# RGMII_PHY.net
KiCad netlist of a schematic drawn in Altium Designer
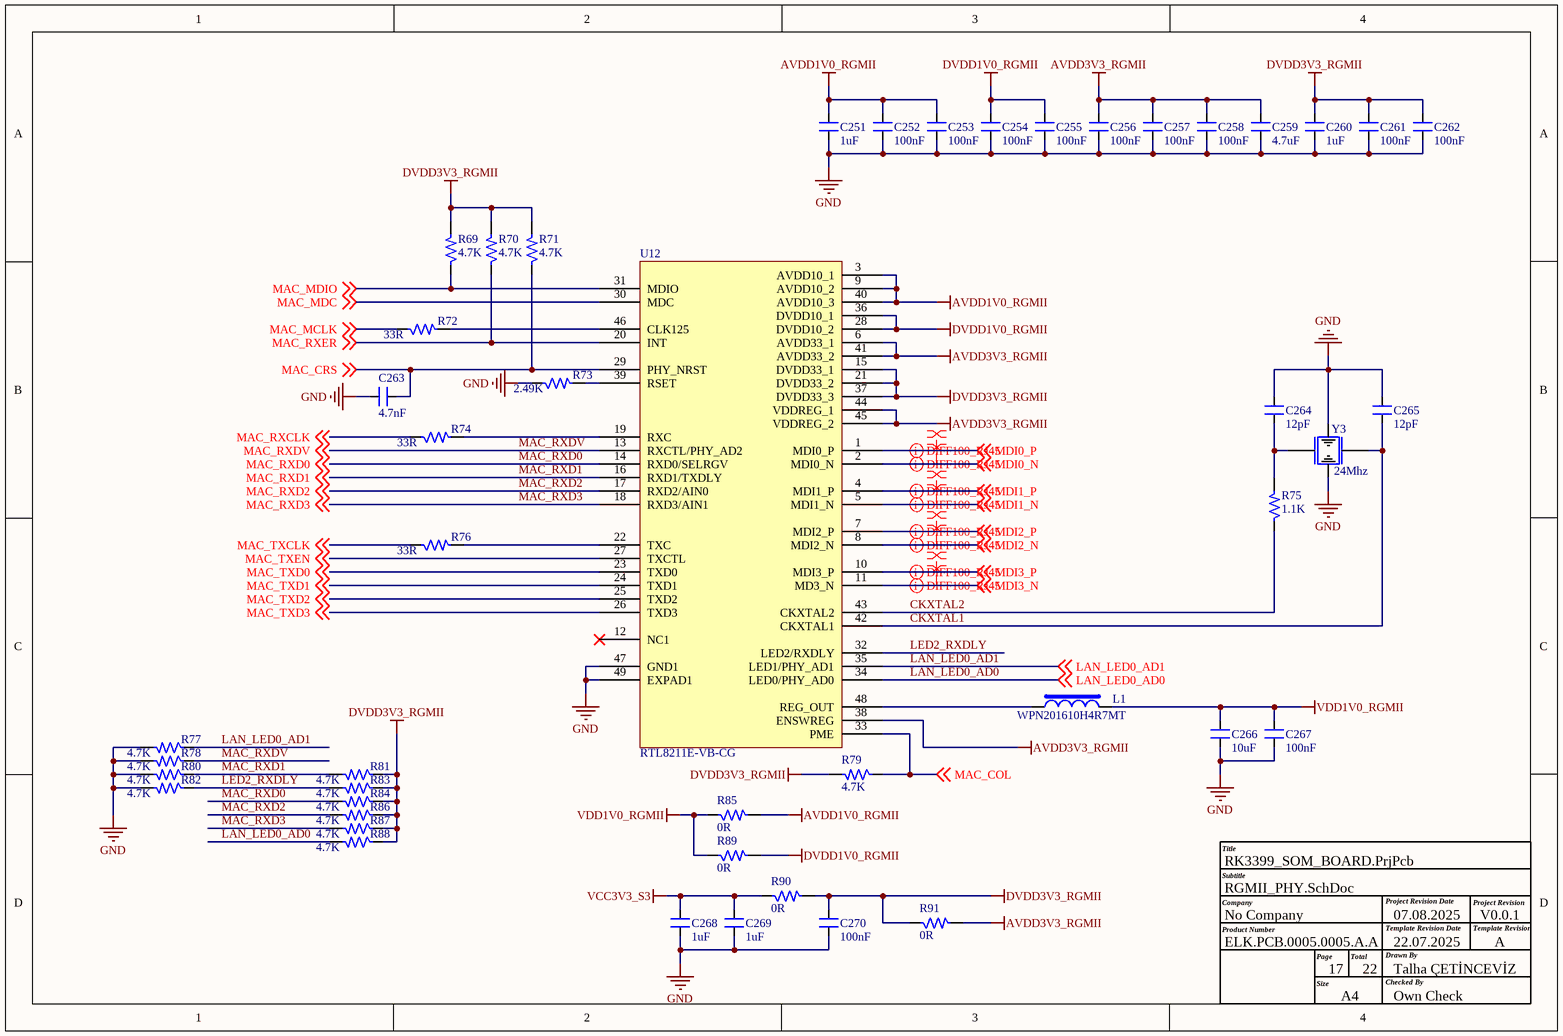
[diagram p0: RGMII_PHY.SchDoc]

(export (version "E")
  (design (tool "Eeschema 10.0.6"))
  (components
    (comp (ref "C251")
      (value "1uF")
      (footprint "CAP_0201")
      (description "1µF ±20% 16V Ceramic Capacitor X5R 0201 (0603 Metric)")
      (fields
        (field (name "MANUFACTURER") "Samsung Electro-Mechanics")
        (field (name "MANUFACTURER PART NUMBER") "CL03A105MO3NRNH")
      )
      (libsource (lib "EsteemPCB_SOM_Course_intlib") (part "CAP_1uF-16V-10%-0201"))
    )
    (comp (ref "C252")
      (value "100nF")
      (footprint "CAP_0201")
      (description "0.1µF ±10% 25V Ceramic Capacitor X5R 0201 (0603 Metric)")
      (fields
        (field (name "MANUFACTURER") "TDK Corporation")
        (field (name "MANUFACTURER PART NUMBER") "C0603X5R1E104K030BB")
      )
      (libsource (lib "EsteemPCB_SOM_Course_intlib") (part "CAP_100nF-25V-10%-0201"))
    )
    (comp (ref "C253")
      (value "100nF")
      (footprint "CAP_0201")
      (description "0.1µF ±10% 25V Ceramic Capacitor X5R 0201 (0603 Metric)")
      (fields
        (field (name "MANUFACTURER") "TDK Corporation")
        (field (name "MANUFACTURER PART NUMBER") "C0603X5R1E104K030BB")
      )
      (libsource (lib "EsteemPCB_SOM_Course_intlib") (part "CAP_100nF-25V-10%-0201"))
    )
    (comp (ref "C254")
      (value "100nF")
      (footprint "CAP_0201")
      (description "0.1µF ±10% 25V Ceramic Capacitor X5R 0201 (0603 Metric)")
      (fields
        (field (name "MANUFACTURER") "TDK Corporation")
        (field (name "MANUFACTURER PART NUMBER") "C0603X5R1E104K030BB")
      )
      (libsource (lib "EsteemPCB_SOM_Course_intlib") (part "CAP_100nF-25V-10%-0201"))
    )
    (comp (ref "C255")
      (value "100nF")
      (footprint "CAP_0201")
      (description "0.1µF ±10% 25V Ceramic Capacitor X5R 0201 (0603 Metric)")
      (fields
        (field (name "MANUFACTURER") "TDK Corporation")
        (field (name "MANUFACTURER PART NUMBER") "C0603X5R1E104K030BB")
      )
      (libsource (lib "EsteemPCB_SOM_Course_intlib") (part "CAP_100nF-25V-10%-0201"))
    )
    (comp (ref "C256")
      (value "100nF")
      (footprint "CAP_0201")
      (description "0.1µF ±10% 25V Ceramic Capacitor X5R 0201 (0603 Metric)")
      (fields
        (field (name "MANUFACTURER") "TDK Corporation")
        (field (name "MANUFACTURER PART NUMBER") "C0603X5R1E104K030BB")
      )
      (libsource (lib "EsteemPCB_SOM_Course_intlib") (part "CAP_100nF-25V-10%-0201"))
    )
    (comp (ref "C257")
      (value "100nF")
      (footprint "CAP_0201")
      (description "0.1µF ±10% 25V Ceramic Capacitor X5R 0201 (0603 Metric)")
      (fields
        (field (name "MANUFACTURER") "TDK Corporation")
        (field (name "MANUFACTURER PART NUMBER") "C0603X5R1E104K030BB")
      )
      (libsource (lib "EsteemPCB_SOM_Course_intlib") (part "CAP_100nF-25V-10%-0201"))
    )
    (comp (ref "C258")
      (value "100nF")
      (footprint "CAP_0201")
      (description "0.1µF ±10% 25V Ceramic Capacitor X5R 0201 (0603 Metric)")
      (fields
        (field (name "MANUFACTURER") "TDK Corporation")
        (field (name "MANUFACTURER PART NUMBER") "C0603X5R1E104K030BB")
      )
      (libsource (lib "EsteemPCB_SOM_Course_intlib") (part "CAP_100nF-25V-10%-0201"))
    )
    (comp (ref "C259")
      (value "4.7uF")
      (footprint "CAP_0201")
      (description "4.7µF ±20% 6.3V Ceramic Capacitor X5R 0201 (0603 Metric)")
      (fields
        (field (name "MANUFACTURER") "Murata Electronics")
        (field (name "MANUFACTURER PART NUMBER") "GRM035R60J475ME15D")
      )
      (libsource (lib "EsteemPCB_SOM_Course_intlib") (part "CAP_4.7uF-6.3V-20%-0201"))
    )
    (comp (ref "C260")
      (value "1uF")
      (footprint "CAP_0201")
      (description "1µF ±20% 16V Ceramic Capacitor X5R 0201 (0603 Metric)")
      (fields
        (field (name "MANUFACTURER") "Samsung Electro-Mechanics")
        (field (name "MANUFACTURER PART NUMBER") "CL03A105MO3NRNH")
      )
      (libsource (lib "EsteemPCB_SOM_Course_intlib") (part "CAP_1uF-16V-10%-0201"))
    )
    (comp (ref "C261")
      (value "100nF")
      (footprint "CAP_0201")
      (description "0.1µF ±10% 25V Ceramic Capacitor X5R 0201 (0603 Metric)")
      (fields
        (field (name "MANUFACTURER") "TDK Corporation")
        (field (name "MANUFACTURER PART NUMBER") "C0603X5R1E104K030BB")
      )
      (libsource (lib "EsteemPCB_SOM_Course_intlib") (part "CAP_100nF-25V-10%-0201"))
    )
    (comp (ref "C262")
      (value "100nF")
      (footprint "CAP_0201")
      (description "0.1µF ±10% 25V Ceramic Capacitor X5R 0201 (0603 Metric)")
      (fields
        (field (name "MANUFACTURER") "TDK Corporation")
        (field (name "MANUFACTURER PART NUMBER") "C0603X5R1E104K030BB")
      )
      (libsource (lib "EsteemPCB_SOM_Course_intlib") (part "CAP_100nF-25V-10%-0201"))
    )
    (comp (ref "C263")
      (value "4.7nF")
      (footprint "CAP_0201")
      (description "4700pF ±10% 10V Ceramic Capacitor X7R 0201 (0603 Metric)")
      (fields
        (field (name "MANUFACTURER") "AVX Corporation")
        (field (name "MANUFACTURER PART NUMBER") "0201ZC472KAT2A")
      )
      (libsource (lib "EsteemPCB_SOM_Course_intlib") (part "CAP_4.7nF-10V-10%-0201"))
    )
    (comp (ref "C264")
      (value "12pF")
      (footprint "CAP_0201")
      (description "12pF ±10% 16V Ceramic Capacitor C0G, NP0 0201 (0603 Metric)")
      (fields
        (field (name "MANUFACTURER") "AVX Corporation")
        (field (name "MANUFACTURER PART NUMBER") "0201YA120KAT2A")
      )
      (libsource (lib "EsteemPCB_SOM_Course_intlib") (part "CAP_12pF-16V-10%-0201"))
    )
    (comp (ref "C265")
      (value "12pF")
      (footprint "CAP_0201")
      (description "12pF ±10% 16V Ceramic Capacitor C0G, NP0 0201 (0603 Metric)")
      (fields
        (field (name "MANUFACTURER") "AVX Corporation")
        (field (name "MANUFACTURER PART NUMBER") "0201YA120KAT2A")
      )
      (libsource (lib "EsteemPCB_SOM_Course_intlib") (part "CAP_12pF-16V-10%-0201"))
    )
    (comp (ref "C266")
      (value "10uF")
      (footprint "CAP_0402")
      (description "10µF ±20% 10V Ceramic Capacitor X5R 0402 (1005 Metric)")
      (fields
        (field (name "MANUFACTURER PART NUMBER") "CL05A106MP5NUNC")
        (field (name "MANUFACTURER") "Samsung Electro-Mechanics")
      )
      (libsource (lib "EsteemPCB_SOM_Course_intlib") (part "CAP_10uF-10V-20%-0402"))
    )
    (comp (ref "C267")
      (value "100nF")
      (footprint "CAP_0201")
      (description "0.1µF ±10% 25V Ceramic Capacitor X5R 0201 (0603 Metric)")
      (fields
        (field (name "MANUFACTURER") "TDK Corporation")
        (field (name "MANUFACTURER PART NUMBER") "C0603X5R1E104K030BB")
      )
      (libsource (lib "EsteemPCB_SOM_Course_intlib") (part "CAP_100nF-25V-10%-0201"))
    )
    (comp (ref "C268")
      (value "1uF")
      (footprint "CAP_0201")
      (description "1µF ±20% 16V Ceramic Capacitor X5R 0201 (0603 Metric)")
      (fields
        (field (name "MANUFACTURER") "Samsung Electro-Mechanics")
        (field (name "MANUFACTURER PART NUMBER") "CL03A105MO3NRNH")
      )
      (libsource (lib "EsteemPCB_SOM_Course_intlib") (part "CAP_1uF-16V-10%-0201"))
    )
    (comp (ref "C269")
      (value "1uF")
      (footprint "CAP_0201")
      (description "1µF ±20% 16V Ceramic Capacitor X5R 0201 (0603 Metric)")
      (fields
        (field (name "MANUFACTURER") "Samsung Electro-Mechanics")
        (field (name "MANUFACTURER PART NUMBER") "CL03A105MO3NRNH")
      )
      (libsource (lib "EsteemPCB_SOM_Course_intlib") (part "CAP_1uF-16V-10%-0201"))
    )
    (comp (ref "C270")
      (value "100nF")
      (footprint "CAP_0201")
      (description "0.1µF ±10% 25V Ceramic Capacitor X5R 0201 (0603 Metric)")
      (fields
        (field (name "MANUFACTURER") "TDK Corporation")
        (field (name "MANUFACTURER PART NUMBER") "C0603X5R1E104K030BB")
      )
      (libsource (lib "EsteemPCB_SOM_Course_intlib") (part "CAP_100nF-25V-10%-0201"))
    )
    (comp (ref "L1")
      (value "WPN201610H4R7MT")
      (footprint "IND_62.9_110X86.6_SMD")
      (description "4.7uH ±20% 900mA 425mΩ SMD,2.0x1.6x1.0mm Power Inductors RoHS")
      (fields (field (name "MANUFACTURER") "Sunlord"))
      (libsource (lib "EsteemPCB_SOM_Course_intlib") (part "IND_4.7uH-0.9A-20%-SMD"))
    )
    (comp (ref "R69")
      (value "4.7K")
      (footprint "RES_0201")
      (description "4.02 kOhms ±1% 0.05W, 1/20W Chip Resistor 0201 (0603 Metric) Thick Film")
      (fields
        (field (name "MANUFACTURER") "Yageo")
        (field (name "MANUFACTURER PART NUMBER") "RC0201FR-074K02L")
      )
      (libsource (lib "EsteemPCB_SOM_Course_intlib") (part "RES_4.7K-0.1W-1%-0201"))
    )
    (comp (ref "R70")
      (value "4.7K")
      (footprint "RES_0201")
      (description "4.02 kOhms ±1% 0.05W, 1/20W Chip Resistor 0201 (0603 Metric) Thick Film")
      (fields
        (field (name "MANUFACTURER") "Yageo")
        (field (name "MANUFACTURER PART NUMBER") "RC0201FR-074K02L")
      )
      (libsource (lib "EsteemPCB_SOM_Course_intlib") (part "RES_4.7K-0.1W-1%-0201"))
    )
    (comp (ref "R71")
      (value "4.7K")
      (footprint "RES_0201")
      (description "4.02 kOhms ±1% 0.05W, 1/20W Chip Resistor 0201 (0603 Metric) Thick Film")
      (fields
        (field (name "MANUFACTURER") "Yageo")
        (field (name "MANUFACTURER PART NUMBER") "RC0201FR-074K02L")
      )
      (libsource (lib "EsteemPCB_SOM_Course_intlib") (part "RES_4.7K-0.1W-1%-0201"))
    )
    (comp (ref "R72")
      (value "33R")
      (footprint "RES_0201")
      (description "33 Ohms ±1% 0.05W, 1/20W Chip Resistor 0201 (0603 Metric) Thick Film")
      (fields
        (field (name "MANUFACTURER") "Yageo")
        (field (name "MANUFACTURER PART NUMBER") "RC0201FR-0733RL")
      )
      (libsource (lib "EsteemPCB_SOM_Course_intlib") (part "RES_33R-0.05W-1%-0201"))
    )
    (comp (ref "R73")
      (value "2.49K")
      (footprint "RES_0201")
      (description "2.49 kOhms ±1% 0.05W, 1/20W Chip Resistor 0201 (0603 Metric) Automotive AEC-Q200 Thick Film")
      (fields
        (field (name "MANUFACTURER") "Panasonic Electronic Components")
        (field (name "MANUFACTURER PART NUMBER") "ERJ-1GNF2491C")
      )
      (libsource (lib "EsteemPCB_SOM_Course_intlib") (part "RES_2.49K-0.05W-1%-0201"))
    )
    (comp (ref "R74")
      (value "33R")
      (footprint "RES_0201")
      (description "33 Ohms ±1% 0.05W, 1/20W Chip Resistor 0201 (0603 Metric) Thick Film")
      (fields
        (field (name "MANUFACTURER") "Yageo")
        (field (name "MANUFACTURER PART NUMBER") "RC0201FR-0733RL")
      )
      (libsource (lib "EsteemPCB_SOM_Course_intlib") (part "RES_33R-0.05W-1%-0201"))
    )
    (comp (ref "R75")
      (value "1.1K")
      (footprint "RES_0201")
      (description "1.1 kOhms ±1% 0.05W, 1/20W Chip Resistor 0201 (0603 Metric) Automotive AEC-Q200 Thick Film")
      (fields
        (field (name "MANUFACTURER") "Panasonic Electronic Components")
        (field (name "MANUFACTURER PART NUMBER") "ERJ-1GNF1101C")
      )
      (libsource (lib "EsteemPCB_SOM_Course_intlib") (part "RES_1.1K-0.05W-1%-0201"))
    )
    (comp (ref "R76")
      (value "33R")
      (footprint "RES_0201")
      (description "33 Ohms ±1% 0.05W, 1/20W Chip Resistor 0201 (0603 Metric) Thick Film")
      (fields
        (field (name "MANUFACTURER") "Yageo")
        (field (name "MANUFACTURER PART NUMBER") "RC0201FR-0733RL")
      )
      (libsource (lib "EsteemPCB_SOM_Course_intlib") (part "RES_33R-0.05W-1%-0201"))
    )
    (comp (ref "R77")
      (value "4.7K")
      (footprint "RES_0201")
      (description "4.02 kOhms ±1% 0.05W, 1/20W Chip Resistor 0201 (0603 Metric) Thick Film")
      (fields
        (field (name "MANUFACTURER") "Yageo")
        (field (name "MANUFACTURER PART NUMBER") "RC0201FR-074K02L")
      )
      (libsource (lib "EsteemPCB_SOM_Course_intlib") (part "RES_4.7K-0.1W-1%-0201"))
    )
    (comp (ref "R78")
      (value "4.7K")
      (footprint "RES_0201")
      (description "4.02 kOhms ±1% 0.05W, 1/20W Chip Resistor 0201 (0603 Metric) Thick Film")
      (fields
        (field (name "MANUFACTURER") "Yageo")
        (field (name "MANUFACTURER PART NUMBER") "RC0201FR-074K02L")
      )
      (libsource (lib "EsteemPCB_SOM_Course_intlib") (part "RES_4.7K-0.1W-1%-0201"))
    )
    (comp (ref "R79")
      (value "4.7K")
      (footprint "RES_0201")
      (description "4.02 kOhms ±1% 0.05W, 1/20W Chip Resistor 0201 (0603 Metric) Thick Film")
      (fields
        (field (name "MANUFACTURER") "Yageo")
        (field (name "MANUFACTURER PART NUMBER") "RC0201FR-074K02L")
      )
      (libsource (lib "EsteemPCB_SOM_Course_intlib") (part "RES_4.7K-0.1W-1%-0201"))
    )
    (comp (ref "R80")
      (value "4.7K")
      (footprint "RES_0201")
      (description "4.02 kOhms ±1% 0.05W, 1/20W Chip Resistor 0201 (0603 Metric) Thick Film")
      (fields
        (field (name "MANUFACTURER") "Yageo")
        (field (name "MANUFACTURER PART NUMBER") "RC0201FR-074K02L")
      )
      (libsource (lib "EsteemPCB_SOM_Course_intlib") (part "RES_4.7K-0.1W-1%-0201"))
    )
    (comp (ref "R81")
      (value "4.7K")
      (footprint "RES_0201")
      (description "4.02 kOhms ±1% 0.05W, 1/20W Chip Resistor 0201 (0603 Metric) Thick Film")
      (fields
        (field (name "MANUFACTURER") "Yageo")
        (field (name "MANUFACTURER PART NUMBER") "RC0201FR-074K02L")
      )
      (libsource (lib "EsteemPCB_SOM_Course_intlib") (part "RES_4.7K-0.1W-1%-0201"))
    )
    (comp (ref "R82")
      (value "4.7K")
      (footprint "RES_0201")
      (description "4.02 kOhms ±1% 0.05W, 1/20W Chip Resistor 0201 (0603 Metric) Thick Film")
      (fields
        (field (name "MANUFACTURER") "Yageo")
        (field (name "MANUFACTURER PART NUMBER") "RC0201FR-074K02L")
      )
      (libsource (lib "EsteemPCB_SOM_Course_intlib") (part "RES_4.7K-0.1W-1%-0201"))
    )
    (comp (ref "R83")
      (value "4.7K")
      (footprint "RES_0201")
      (description "4.02 kOhms ±1% 0.05W, 1/20W Chip Resistor 0201 (0603 Metric) Thick Film")
      (fields
        (field (name "MANUFACTURER") "Yageo")
        (field (name "MANUFACTURER PART NUMBER") "RC0201FR-074K02L")
      )
      (libsource (lib "EsteemPCB_SOM_Course_intlib") (part "RES_4.7K-0.1W-1%-0201"))
    )
    (comp (ref "R84")
      (value "4.7K")
      (footprint "RES_0201")
      (description "4.02 kOhms ±1% 0.05W, 1/20W Chip Resistor 0201 (0603 Metric) Thick Film")
      (fields
        (field (name "MANUFACTURER") "Yageo")
        (field (name "MANUFACTURER PART NUMBER") "RC0201FR-074K02L")
      )
      (libsource (lib "EsteemPCB_SOM_Course_intlib") (part "RES_4.7K-0.1W-1%-0201"))
    )
    (comp (ref "R85")
      (value "0R")
      (footprint "RES_0201")
      (description "0 Ohms Jumper 0.05W, 1/20W Chip Resistor 0201 (0603 Metric) Automotive AEC-Q200 Thick Film")
      (fields
        (field (name "MANUFACTURER") "Bourns Inc.")
        (field (name "MANUFACTURER PART NUMBER") "CR0201AJ/-000GLF")
      )
      (libsource (lib "EsteemPCB_SOM_Course_intlib") (part "RES_0R-0.05W-1%-0201"))
    )
    (comp (ref "R86")
      (value "4.7K")
      (footprint "RES_0201")
      (description "4.02 kOhms ±1% 0.05W, 1/20W Chip Resistor 0201 (0603 Metric) Thick Film")
      (fields
        (field (name "MANUFACTURER") "Yageo")
        (field (name "MANUFACTURER PART NUMBER") "RC0201FR-074K02L")
      )
      (libsource (lib "EsteemPCB_SOM_Course_intlib") (part "RES_4.7K-0.1W-1%-0201"))
    )
    (comp (ref "R87")
      (value "4.7K")
      (footprint "RES_0201")
      (description "4.02 kOhms ±1% 0.05W, 1/20W Chip Resistor 0201 (0603 Metric) Thick Film")
      (fields
        (field (name "MANUFACTURER") "Yageo")
        (field (name "MANUFACTURER PART NUMBER") "RC0201FR-074K02L")
      )
      (libsource (lib "EsteemPCB_SOM_Course_intlib") (part "RES_4.7K-0.1W-1%-0201"))
    )
    (comp (ref "R88")
      (value "4.7K")
      (footprint "RES_0201")
      (description "4.02 kOhms ±1% 0.05W, 1/20W Chip Resistor 0201 (0603 Metric) Thick Film")
      (fields
        (field (name "MANUFACTURER") "Yageo")
        (field (name "MANUFACTURER PART NUMBER") "RC0201FR-074K02L")
      )
      (libsource (lib "EsteemPCB_SOM_Course_intlib") (part "RES_4.7K-0.1W-1%-0201"))
    )
    (comp (ref "R89")
      (value "0R")
      (footprint "RES_0201")
      (description "0 Ohms Jumper 0.05W, 1/20W Chip Resistor 0201 (0603 Metric) Automotive AEC-Q200 Thick Film")
      (fields
        (field (name "MANUFACTURER") "Bourns Inc.")
        (field (name "MANUFACTURER PART NUMBER") "CR0201AJ/-000GLF")
      )
      (libsource (lib "EsteemPCB_SOM_Course_intlib") (part "RES_0R-0.05W-1%-0201"))
    )
    (comp (ref "R90")
      (value "0R")
      (footprint "RES_0201")
      (description "0 Ohms Jumper 0.05W, 1/20W Chip Resistor 0201 (0603 Metric) Automotive AEC-Q200 Thick Film")
      (fields
        (field (name "MANUFACTURER") "Bourns Inc.")
        (field (name "MANUFACTURER PART NUMBER") "CR0201AJ/-000GLF")
      )
      (libsource (lib "EsteemPCB_SOM_Course_intlib") (part "RES_0R-0.05W-1%-0201"))
    )
    (comp (ref "R91")
      (value "0R")
      (footprint "RES_0201")
      (description "0 Ohms Jumper 0.05W, 1/20W Chip Resistor 0201 (0603 Metric) Automotive AEC-Q200 Thick Film")
      (fields
        (field (name "MANUFACTURER") "Bourns Inc.")
        (field (name "MANUFACTURER PART NUMBER") "CR0201AJ/-000GLF")
      )
      (libsource (lib "EsteemPCB_SOM_Course_intlib") (part "RES_0R-0.05W-1%-0201"))
    )
    (comp (ref "U12")
      (value "RTL8211E-VB-CG")
      (footprint "QFN48_19.6_324X324_SMD")
      (fields (field (name "MANUFACTURER") "Realtek Semicon"))
      (libsource (lib "EsteemPCB_SOM_Course_intlib") (part "IC_RTL8211E-VB-CG"))
    )
    (comp (ref "Y3")
      (value "24Mhz")
      (footprint "XTAL_ABM8AIG-24.000MHZ-12-2Z-T3")
      (description "24MHz ±20ppm Crystal 12pF 50 Ohms 4-SMD, No Lead")
      (fields
        (field (name "MANUFACTURER") "Abracon LLC")
        (field (name "MANUFACTURER PART NUMBER") "ABM8AIG-24.000MHZ-12-2Z-T3")
      )
      (libsource (lib "EsteemPCB_SOM_Course_intlib") (part "XTAL_24Mhz-12pF-4-SMD"))
    )
  )
  (nets
    (net (code "1") (name "/CKXTAL1") (class "Default")
      (node (ref "C265") (pin "2") (pinfunction "2_2") (pintype "passive"))
      (node (ref "U12") (pin "42") (pinfunction "CKXTAL1_42") (pintype "passive"))
      (node (ref "Y3") (pin "1") (pinfunction "1_1") (pintype "passive"))
    )
    (net (code "2") (name "/CKXTAL2") (class "Default")
      (node (ref "R75") (pin "1") (pinfunction "1_1") (pintype "passive"))
      (node (ref "U12") (pin "43") (pinfunction "CKXTAL2_43") (pintype "passive"))
    )
    (net (code "3") (name "/LED2_RXDLY") (class "Default")
      (node (ref "R82") (pin "1") (pinfunction "1_1") (pintype "passive"))
      (node (ref "R83") (pin "2") (pinfunction "2_2") (pintype "passive"))
      (node (ref "U12") (pin "32") (pinfunction "LED2/RXDLY_32") (pintype "passive"))
    )
    (net (code "4") (name "AVDD1V0_RGMII") (class "Default")
      (node (ref "C251") (pin "2") (pinfunction "2_2") (pintype "passive"))
      (node (ref "C252") (pin "2") (pinfunction "2_2") (pintype "passive"))
      (node (ref "C253") (pin "2") (pinfunction "2_2") (pintype "passive"))
      (node (ref "R85") (pin "2") (pinfunction "2_2") (pintype "passive"))
      (node (ref "U12") (pin "3") (pinfunction "AVDD10_1_3") (pintype "passive"))
      (node (ref "U12") (pin "40") (pinfunction "AVDD10_3_40") (pintype "passive"))
      (node (ref "U12") (pin "9") (pinfunction "AVDD10_2_9") (pintype "passive"))
    )
    (net (code "5") (name "AVDD3V3_RGMII") (class "Default")
      (node (ref "C256") (pin "2") (pinfunction "2_2") (pintype "passive"))
      (node (ref "C257") (pin "2") (pinfunction "2_2") (pintype "passive"))
      (node (ref "C258") (pin "2") (pinfunction "2_2") (pintype "passive"))
      (node (ref "C259") (pin "2") (pinfunction "2_2") (pintype "passive"))
      (node (ref "R91") (pin "2") (pinfunction "2_2") (pintype "passive"))
      (node (ref "U12") (pin "38") (pinfunction "ENSWREG_38") (pintype "passive"))
      (node (ref "U12") (pin "41") (pinfunction "AVDD33_2_41") (pintype "passive"))
      (node (ref "U12") (pin "44") (pinfunction "VDDREG_1_44") (pintype "passive"))
      (node (ref "U12") (pin "45") (pinfunction "VDDREG_2_45") (pintype "passive"))
      (node (ref "U12") (pin "6") (pinfunction "AVDD33_1_6") (pintype "passive"))
    )
    (net (code "6") (name "DVDD1V0_RGMII") (class "Default")
      (node (ref "C254") (pin "2") (pinfunction "2_2") (pintype "passive"))
      (node (ref "C255") (pin "2") (pinfunction "2_2") (pintype "passive"))
      (node (ref "R89") (pin "2") (pinfunction "2_2") (pintype "passive"))
      (node (ref "U12") (pin "28") (pinfunction "DVDD10_2_28") (pintype "passive"))
      (node (ref "U12") (pin "36") (pinfunction "DVDD10_1_36") (pintype "passive"))
    )
    (net (code "7") (name "DVDD3V3_RGMII") (class "Default")
      (node (ref "C260") (pin "2") (pinfunction "2_2") (pintype "passive"))
      (node (ref "C261") (pin "2") (pinfunction "2_2") (pintype "passive"))
      (node (ref "C262") (pin "2") (pinfunction "2_2") (pintype "passive"))
      (node (ref "C270") (pin "2") (pinfunction "2_2") (pintype "passive"))
      (node (ref "R69") (pin "2") (pinfunction "2_2") (pintype "passive"))
      (node (ref "R70") (pin "2") (pinfunction "2_2") (pintype "passive"))
      (node (ref "R71") (pin "2") (pinfunction "2_2") (pintype "passive"))
      (node (ref "R79") (pin "2") (pinfunction "2_2") (pintype "passive"))
      (node (ref "R81") (pin "1") (pinfunction "1_1") (pintype "passive"))
      (node (ref "R83") (pin "1") (pinfunction "1_1") (pintype "passive"))
      (node (ref "R84") (pin "1") (pinfunction "1_1") (pintype "passive"))
      (node (ref "R86") (pin "1") (pinfunction "1_1") (pintype "passive"))
      (node (ref "R87") (pin "1") (pinfunction "1_1") (pintype "passive"))
      (node (ref "R88") (pin "1") (pinfunction "1_1") (pintype "passive"))
      (node (ref "R90") (pin "2") (pinfunction "2_2") (pintype "passive"))
      (node (ref "R91") (pin "1") (pinfunction "1_1") (pintype "passive"))
      (node (ref "U12") (pin "15") (pinfunction "DVDD33_1_15") (pintype "passive"))
      (node (ref "U12") (pin "21") (pinfunction "DVDD33_2_21") (pintype "passive"))
      (node (ref "U12") (pin "37") (pinfunction "DVDD33_3_37") (pintype "passive"))
    )
    (net (code "8") (name "GND") (class "Default")
      (node (ref "C251") (pin "1") (pinfunction "1_1") (pintype "passive"))
      (node (ref "C252") (pin "1") (pinfunction "1_1") (pintype "passive"))
      (node (ref "C253") (pin "1") (pinfunction "1_1") (pintype "passive"))
      (node (ref "C254") (pin "1") (pinfunction "1_1") (pintype "passive"))
      (node (ref "C255") (pin "1") (pinfunction "1_1") (pintype "passive"))
      (node (ref "C256") (pin "1") (pinfunction "1_1") (pintype "passive"))
      (node (ref "C257") (pin "1") (pinfunction "1_1") (pintype "passive"))
      (node (ref "C258") (pin "1") (pinfunction "1_1") (pintype "passive"))
      (node (ref "C259") (pin "1") (pinfunction "1_1") (pintype "passive"))
      (node (ref "C260") (pin "1") (pinfunction "1_1") (pintype "passive"))
      (node (ref "C261") (pin "1") (pinfunction "1_1") (pintype "passive"))
      (node (ref "C262") (pin "1") (pinfunction "1_1") (pintype "passive"))
      (node (ref "C263") (pin "2") (pinfunction "2_2") (pintype "passive"))
      (node (ref "C264") (pin "1") (pinfunction "1_1") (pintype "passive"))
      (node (ref "C265") (pin "1") (pinfunction "1_1") (pintype "passive"))
      (node (ref "C266") (pin "1") (pinfunction "1_1") (pintype "passive"))
      (node (ref "C267") (pin "1") (pinfunction "1_1") (pintype "passive"))
      (node (ref "C268") (pin "1") (pinfunction "1_1") (pintype "passive"))
      (node (ref "C269") (pin "1") (pinfunction "1_1") (pintype "passive"))
      (node (ref "C270") (pin "1") (pinfunction "1_1") (pintype "passive"))
      (node (ref "R73") (pin "1") (pinfunction "1_1") (pintype "passive"))
      (node (ref "R77") (pin "2") (pinfunction "2_2") (pintype "passive"))
      (node (ref "R78") (pin "2") (pinfunction "2_2") (pintype "passive"))
      (node (ref "R80") (pin "2") (pinfunction "2_2") (pintype "passive"))
      (node (ref "R82") (pin "2") (pinfunction "2_2") (pintype "passive"))
      (node (ref "U12") (pin "47") (pinfunction "GND1_47") (pintype "passive"))
      (node (ref "U12") (pin "49") (pinfunction "EXPAD1_49") (pintype "passive"))
      (node (ref "Y3") (pin "2") (pinfunction "2_2") (pintype "passive"))
      (node (ref "Y3") (pin "4") (pinfunction "4_4") (pintype "passive"))
    )
    (net (code "9") (name "LAN_LED0_AD0") (class "Default")
      (node (ref "R88") (pin "2") (pinfunction "2_2") (pintype "passive"))
      (node (ref "U12") (pin "34") (pinfunction "LED0/PHY_AD0_34") (pintype "passive"))
    )
    (net (code "10") (name "LAN_LED0_AD1") (class "Default")
      (node (ref "R77") (pin "1") (pinfunction "1_1") (pintype "passive"))
      (node (ref "U12") (pin "35") (pinfunction "LED1/PHY_AD1_35") (pintype "passive"))
    )
    (net (code "11") (name "MAC_COL") (class "Default")
      (node (ref "R79") (pin "1") (pinfunction "1_1") (pintype "passive"))
      (node (ref "U12") (pin "33") (pinfunction "PME_33") (pintype "passive"))
    )
    (net (code "12") (name "MAC_CRS") (class "Default")
      (node (ref "C263") (pin "1") (pinfunction "1_1") (pintype "passive"))
      (node (ref "R71") (pin "1") (pinfunction "1_1") (pintype "passive"))
      (node (ref "U12") (pin "29") (pinfunction "PHY_NRST_29") (pintype "passive"))
    )
    (net (code "13") (name "MAC_MCLK") (class "Default")
      (node (ref "R72") (pin "1") (pinfunction "1_1") (pintype "passive"))
    )
    (net (code "14") (name "MAC_MDC") (class "Default")
      (node (ref "U12") (pin "30") (pinfunction "MDC_30") (pintype "passive"))
    )
    (net (code "15") (name "MAC_MDIO") (class "Default")
      (node (ref "R69") (pin "1") (pinfunction "1_1") (pintype "passive"))
      (node (ref "U12") (pin "31") (pinfunction "MDIO_31") (pintype "passive"))
    )
    (net (code "16") (name "MAC_RXCLK") (class "Default")
      (node (ref "R74") (pin "1") (pinfunction "1_1") (pintype "passive"))
    )
    (net (code "17") (name "MAC_RXD0") (class "Default")
      (node (ref "R84") (pin "2") (pinfunction "2_2") (pintype "passive"))
      (node (ref "U12") (pin "14") (pinfunction "RXD0/SELRGV_14") (pintype "passive"))
    )
    (net (code "18") (name "MAC_RXD1") (class "Default")
      (node (ref "R80") (pin "1") (pinfunction "1_1") (pintype "passive"))
      (node (ref "R81") (pin "2") (pinfunction "2_2") (pintype "passive"))
      (node (ref "U12") (pin "16") (pinfunction "RXD1/TXDLY_16") (pintype "passive"))
    )
    (net (code "19") (name "MAC_RXD2") (class "Default")
      (node (ref "R86") (pin "2") (pinfunction "2_2") (pintype "passive"))
      (node (ref "U12") (pin "17") (pinfunction "RXD2/AIN0_17") (pintype "passive"))
    )
    (net (code "20") (name "MAC_RXD3") (class "Default")
      (node (ref "R87") (pin "2") (pinfunction "2_2") (pintype "passive"))
      (node (ref "U12") (pin "18") (pinfunction "RXD3/AIN1_18") (pintype "passive"))
    )
    (net (code "21") (name "MAC_RXDV") (class "Default")
      (node (ref "R78") (pin "1") (pinfunction "1_1") (pintype "passive"))
      (node (ref "U12") (pin "13") (pinfunction "RXCTL/PHY_AD2_13") (pintype "passive"))
    )
    (net (code "22") (name "MAC_RXER") (class "Default")
      (node (ref "R70") (pin "1") (pinfunction "1_1") (pintype "passive"))
      (node (ref "U12") (pin "20") (pinfunction "INT_20") (pintype "passive"))
    )
    (net (code "23") (name "MAC_TXCLK") (class "Default")
      (node (ref "R76") (pin "1") (pinfunction "1_1") (pintype "passive"))
    )
    (net (code "24") (name "MAC_TXD0") (class "Default")
      (node (ref "U12") (pin "23") (pinfunction "TXD0_23") (pintype "passive"))
    )
    (net (code "25") (name "MAC_TXD1") (class "Default")
      (node (ref "U12") (pin "24") (pinfunction "TXD1_24") (pintype "passive"))
    )
    (net (code "26") (name "MAC_TXD2") (class "Default")
      (node (ref "U12") (pin "25") (pinfunction "TXD2_25") (pintype "passive"))
    )
    (net (code "27") (name "MAC_TXD3") (class "Default")
      (node (ref "U12") (pin "26") (pinfunction "TXD3_26") (pintype "passive"))
    )
    (net (code "28") (name "MAC_TXEN") (class "Default")
      (node (ref "U12") (pin "27") (pinfunction "TXCTL_27") (pintype "passive"))
    )
    (net (code "29") (name "MDI0_N") (class "Default")
      (node (ref "U12") (pin "2") (pinfunction "MDI0_N_2") (pintype "passive"))
    )
    (net (code "30") (name "MDI0_P") (class "Default")
      (node (ref "U12") (pin "1") (pinfunction "MDI0_P_1") (pintype "passive"))
    )
    (net (code "31") (name "MDI1_N") (class "Default")
      (node (ref "U12") (pin "5") (pinfunction "MDI1_N_5") (pintype "passive"))
    )
    (net (code "32") (name "MDI1_P") (class "Default")
      (node (ref "U12") (pin "4") (pinfunction "MDI1_P_4") (pintype "passive"))
    )
    (net (code "33") (name "MDI2_N") (class "Default")
      (node (ref "U12") (pin "8") (pinfunction "MDI2_N_8") (pintype "passive"))
    )
    (net (code "34") (name "MDI2_P") (class "Default")
      (node (ref "U12") (pin "7") (pinfunction "MDI2_P_7") (pintype "passive"))
    )
    (net (code "35") (name "MDI3_N") (class "Default")
      (node (ref "U12") (pin "11") (pinfunction "MD3_N_11") (pintype "passive"))
    )
    (net (code "36") (name "MDI3_P") (class "Default")
      (node (ref "U12") (pin "10") (pinfunction "MDI3_P_10") (pintype "passive"))
    )
    (net (code "37") (name "Net-(C264-Pad2)") (class "Default")
      (node (ref "C264") (pin "2") (pinfunction "2_2") (pintype "passive"))
      (node (ref "R75") (pin "2") (pinfunction "2_2") (pintype "passive"))
      (node (ref "Y3") (pin "3") (pinfunction "3_3") (pintype "passive"))
    )
    (net (code "38") (name "Net-(U12-CLK125)") (class "Default")
      (node (ref "R72") (pin "2") (pinfunction "2_2") (pintype "passive"))
      (node (ref "U12") (pin "46") (pinfunction "CLK125_46") (pintype "passive"))
    )
    (net (code "39") (name "Net-(U12-REG_OUT)") (class "Default")
      (node (ref "L1") (pin "1") (pinfunction "1_1") (pintype "passive"))
      (node (ref "U12") (pin "48") (pinfunction "REG_OUT_48") (pintype "passive"))
    )
    (net (code "40") (name "Net-(U12-RSET)") (class "Default")
      (node (ref "R73") (pin "2") (pinfunction "2_2") (pintype "passive"))
      (node (ref "U12") (pin "39") (pinfunction "RSET_39") (pintype "passive"))
    )
    (net (code "41") (name "Net-(U12-RXC)") (class "Default")
      (node (ref "R74") (pin "2") (pinfunction "2_2") (pintype "passive"))
      (node (ref "U12") (pin "19") (pinfunction "RXC_19") (pintype "passive"))
    )
    (net (code "42") (name "Net-(U12-TXC)") (class "Default")
      (node (ref "R76") (pin "2") (pinfunction "2_2") (pintype "passive"))
      (node (ref "U12") (pin "22") (pinfunction "TXC_22") (pintype "passive"))
    )
    (net (code "43") (name "VCC3V3_S3") (class "Default")
      (node (ref "C268") (pin "2") (pinfunction "2_2") (pintype "passive"))
      (node (ref "C269") (pin "2") (pinfunction "2_2") (pintype "passive"))
      (node (ref "R90") (pin "1") (pinfunction "1_1") (pintype "passive"))
    )
    (net (code "44") (name "VDD1V0_RGMII") (class "Default")
      (node (ref "C266") (pin "2") (pinfunction "2_2") (pintype "passive"))
      (node (ref "C267") (pin "2") (pinfunction "2_2") (pintype "passive"))
      (node (ref "L1") (pin "2") (pinfunction "2_2") (pintype "passive"))
      (node (ref "R85") (pin "1") (pinfunction "1_1") (pintype "passive"))
      (node (ref "R89") (pin "1") (pinfunction "1_1") (pintype "passive"))
    )
    (net (code "45") (name "unconnected-(U12-NC1-Pad12)") (class "Default")
      (node (ref "U12") (pin "12") (pinfunction "NC1_12") (pintype "passive+no_connect"))
    )
  )
)
